# IO_CTRL.net
KiCad netlist of a schematic drawn in Altium Designer
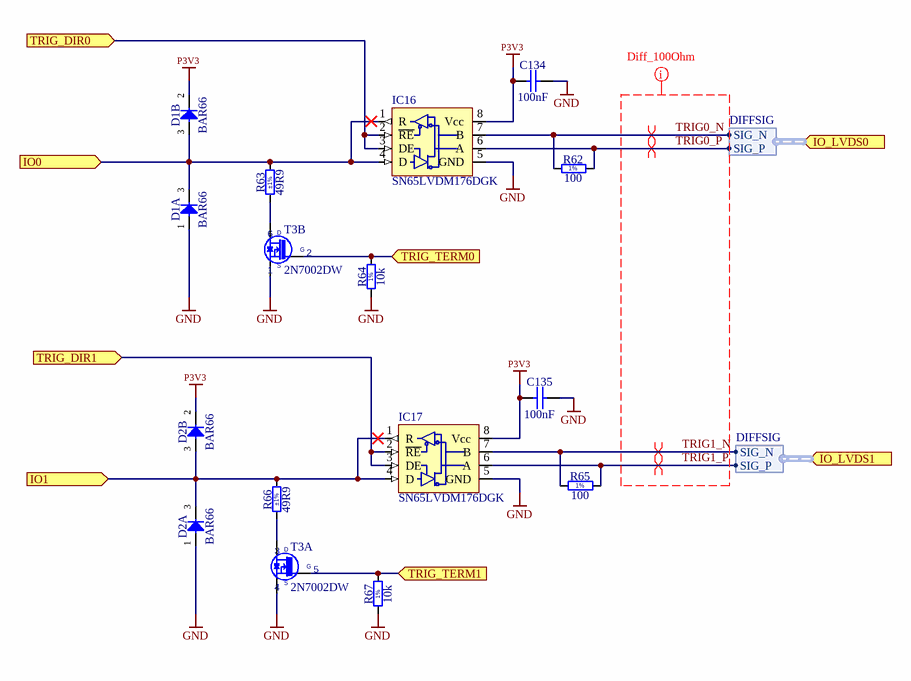
[diagram p0: IO_CTRL.SchDoc]

(export (version "E")
  (design (tool "Eeschema 10.0.6"))
  (components
    (comp (ref "C134")
      (value "100nF")
      (footprint "CAPC1005X55N")
      (description "Non-polarised capacitor")
      (fields
        (field (name "PART NUMBER") "CC0402_100NF_16V_10%_X5R")
        (field (name "VOLTAGE") "16V")
        (field (name "AUTHOR") "CERN DEM JLC")
      )
      (libsource (lib "Capacitors") (part "Capacitor - non polarized"))
    )
    (comp (ref "C135")
      (value "100nF")
      (footprint "CAPC1005X55N")
      (description "Non-polarised capacitor")
      (fields
        (field (name "PART NUMBER") "CC0402_100NF_16V_10%_X5R")
        (field (name "VOLTAGE") "16V")
        (field (name "AUTHOR") "CERN DEM JLC")
      )
      (libsource (lib "Capacitors") (part "Capacitor - non polarized"))
    )
    (comp (ref "D1")
      (value "BAR66")
      (footprint "SOT95P240X110-3N")
      (description "Serial Diode")
      (fields
        (field (name "VOLTAGE") "150V")
        (field (name "POWER") "250mA")
        (field (name "AUTHOR") "CERN DEM JLC")
      )
      (libsource (lib "ICs And Semiconductors") (part "Diode x2 A1C3_A3C2"))
    )
    (comp (ref "D2")
      (value "BAR66")
      (footprint "SOT95P240X110-3N")
      (description "Serial Diode")
      (fields
        (field (name "VOLTAGE") "150V")
        (field (name "POWER") "250mA")
        (field (name "AUTHOR") "CERN DEM JLC")
      )
      (libsource (lib "ICs And Semiconductors") (part "Diode x2 A1C3_A3C2"))
    )
    (comp (ref "IC16")
      (value "SN65LVDM176DGK")
      (footprint "MSOP8 TI/AD")
      (description "High Speed Differential Transceiver LVDS/LVTTL")
      (libsource (lib "Buffers & Drivers") (part "SN65LVDM176"))
    )
    (comp (ref "IC17")
      (value "SN65LVDM176DGK")
      (footprint "MSOP8 TI/AD")
      (description "High Speed Differential Transceiver LVDS/LVTTL")
      (libsource (lib "Buffers & Drivers") (part "SN65LVDM176"))
    )
    (comp (ref "R62")
      (value "100")
      (footprint "RESC0603X28N")
      (description "Resistor - 1%")
      (fields
        (field (name "PART NUMBER") "R0201_100R_1%_0.05W_200PPM")
        (field (name "POWER") "0.05W")
        (field (name "AUTHOR") "CERN DEM JLC")
      )
      (libsource (lib "Resistors") (part "Resistor - 1%"))
    )
    (comp (ref "R63")
      (value "49R9")
      (footprint "RESC3225X70N")
      (description "Resistor - 1%")
      (fields
        (field (name "TOLERANCE") "±1%")
        (field (name "PART NUMBER") "R1210_49R9_1%_0.5W_100PPM_VISHAY_CRCW")
        (field (name "POWER") "0.5W")
        (field (name "AUTHOR") "CERN DEM JMW")
      )
      (libsource (lib "") (part "Resistor - 1%_1"))
    )
    (comp (ref "R64")
      (value "10k")
      (footprint "RESC1005X40N")
      (description "Resistor - 1%")
      (fields
        (field (name "PART NUMBER") "R0402_10K_1%_0.0625W_100PPM")
        (field (name "POWER") "0.0625W")
        (field (name "AUTHOR") "CERN DEM JLC")
      )
      (libsource (lib "Resistors") (part "Resistor - 1%"))
    )
    (comp (ref "R65")
      (value "100")
      (footprint "RESC0603X28N")
      (description "Resistor - 1%")
      (fields
        (field (name "PART NUMBER") "R0201_100R_1%_0.05W_200PPM")
        (field (name "POWER") "0.05W")
        (field (name "AUTHOR") "CERN DEM JLC")
      )
      (libsource (lib "Resistors") (part "Resistor - 1%"))
    )
    (comp (ref "R66")
      (value "49R9")
      (footprint "RESC3225X70N")
      (description "Resistor - 1%")
      (fields
        (field (name "TOLERANCE") "±1%")
        (field (name "PART NUMBER") "R1210_49R9_1%_0.5W_100PPM_VISHAY_CRCW")
        (field (name "POWER") "0.5W")
        (field (name "AUTHOR") "CERN DEM JMW")
      )
      (libsource (lib "") (part "Resistor - 1%_1"))
    )
    (comp (ref "R67")
      (value "10k")
      (footprint "RESC1005X40N")
      (description "Resistor - 1%")
      (fields
        (field (name "PART NUMBER") "R0402_10K_1%_0.0625W_100PPM")
        (field (name "POWER") "0.0625W")
        (field (name "AUTHOR") "CERN DEM JLC")
      )
      (libsource (lib "Resistors") (part "Resistor - 1%"))
    )
    (comp (ref "T3")
      (value "2N7002DW")
      (footprint "SOT65P210X110-6N")
      (description "60 V, 115 mA, Dual N-Channel Field Effect Transistor, Enhancement Mode")
      (fields (field (name "MANUFACTURER") "ON SEMICONDUCTOR") (field (name "AUTHOR") "CERN DEM BC"))
      (libsource (lib "ICs And Semiconductors") (part "2N7002DW"))
    )
  )
  (nets
    (net (code "2") (name "/IO0") (class "Default")
      (node (ref "D1") (pin "3") (pinfunction "COMAC_3") (pintype "passive"))
      (node (ref "IC16") (pin "1") (pinfunction "R_1") (pintype "output"))
      (node (ref "IC16") (pin "4") (pinfunction "D_4") (pintype "input"))
      (node (ref "R63") (pin "2") (pinfunction "2_2") (pintype "passive"))
    )
    (net (code "3") (name "/IO1") (class "Default")
      (node (ref "D2") (pin "3") (pinfunction "COMAC_3") (pintype "passive"))
      (node (ref "IC17") (pin "1") (pinfunction "R_1") (pintype "output"))
      (node (ref "IC17") (pin "4") (pinfunction "D_4") (pintype "input"))
      (node (ref "R66") (pin "2") (pinfunction "2_2") (pintype "passive"))
    )
    (net (code "4") (name "/TRIG0_N") (class "Default")
      (node (ref "IC16") (pin "7") (pinfunction "B_7") (pintype "bidirectional"))
      (node (ref "R62") (pin "1") (pinfunction "1_1") (pintype "passive"))
    )
    (net (code "5") (name "/TRIG0_P") (class "Default")
      (node (ref "IC16") (pin "6") (pinfunction "A_6") (pintype "bidirectional"))
      (node (ref "R62") (pin "2") (pinfunction "2_2") (pintype "passive"))
    )
    (net (code "6") (name "/TRIG1_N") (class "Default")
      (node (ref "IC17") (pin "7") (pinfunction "B_7") (pintype "bidirectional"))
      (node (ref "R65") (pin "1") (pinfunction "1_1") (pintype "passive"))
    )
    (net (code "7") (name "/TRIG1_P") (class "Default")
      (node (ref "IC17") (pin "6") (pinfunction "A_6") (pintype "bidirectional"))
      (node (ref "R65") (pin "2") (pinfunction "2_2") (pintype "passive"))
    )
    (net (code "8") (name "/TRIG_DIR0") (class "Default")
      (node (ref "IC16") (pin "2") (pinfunction "~{RE}_2") (pintype "input"))
      (node (ref "IC16") (pin "3") (pinfunction "DE_3") (pintype "input"))
    )
    (net (code "9") (name "/TRIG_DIR1") (class "Default")
      (node (ref "IC17") (pin "2") (pinfunction "~{RE}_2") (pintype "input"))
      (node (ref "IC17") (pin "3") (pinfunction "DE_3") (pintype "input"))
    )
    (net (code "10") (name "/TRIG_TERM0") (class "Default")
      (node (ref "R64") (pin "2") (pinfunction "2_2") (pintype "passive"))
      (node (ref "T3") (pin "2") (pinfunction "G2_2") (pintype "passive"))
    )
    (net (code "11") (name "/TRIG_TERM1") (class "Default")
      (node (ref "R67") (pin "2") (pinfunction "2_2") (pintype "passive"))
      (node (ref "T3") (pin "5") (pinfunction "G1_5") (pintype "passive"))
    )
    (net (code "13") (name "GND") (class "Default")
      (node (ref "C134") (pin "2") (pinfunction "2_2") (pintype "passive"))
      (node (ref "C135") (pin "2") (pinfunction "2_2") (pintype "passive"))
      (node (ref "D1") (pin "1") (pinfunction "A_1") (pintype "passive"))
      (node (ref "D2") (pin "1") (pinfunction "A_1") (pintype "passive"))
      (node (ref "IC16") (pin "5") (pinfunction "GND_5") (pintype "power_in"))
      (node (ref "IC17") (pin "5") (pinfunction "GND_5") (pintype "power_in"))
      (node (ref "R64") (pin "1") (pinfunction "1_1") (pintype "passive"))
      (node (ref "R67") (pin "1") (pinfunction "1_1") (pintype "passive"))
      (node (ref "T3") (pin "1") (pinfunction "S2_1") (pintype "passive"))
      (node (ref "T3") (pin "4") (pinfunction "S1_4") (pintype "passive"))
    )
    (net (code "14") (name "Net-(T3A-D1)") (class "Default")
      (node (ref "R66") (pin "1") (pinfunction "1_1") (pintype "passive"))
      (node (ref "T3") (pin "3") (pinfunction "D1_3") (pintype "passive"))
    )
    (net (code "15") (name "Net-(T3B-D2)") (class "Default")
      (node (ref "R63") (pin "1") (pinfunction "1_1") (pintype "passive"))
      (node (ref "T3") (pin "6") (pinfunction "D2_6") (pintype "passive"))
    )
    (net (code "16") (name "P3V3") (class "Default")
      (node (ref "C134") (pin "1") (pinfunction "1_1") (pintype "passive"))
      (node (ref "C135") (pin "1") (pinfunction "1_1") (pintype "passive"))
      (node (ref "D1") (pin "2") (pinfunction "C_2") (pintype "passive"))
      (node (ref "D2") (pin "2") (pinfunction "C_2") (pintype "passive"))
      (node (ref "IC16") (pin "8") (pinfunction "Vcc_8") (pintype "power_in"))
      (node (ref "IC17") (pin "8") (pinfunction "Vcc_8") (pintype "power_in"))
    )
  )
)
